# CONFIG_MCU.net
KiCad netlist of a schematic drawn in Altium Designer
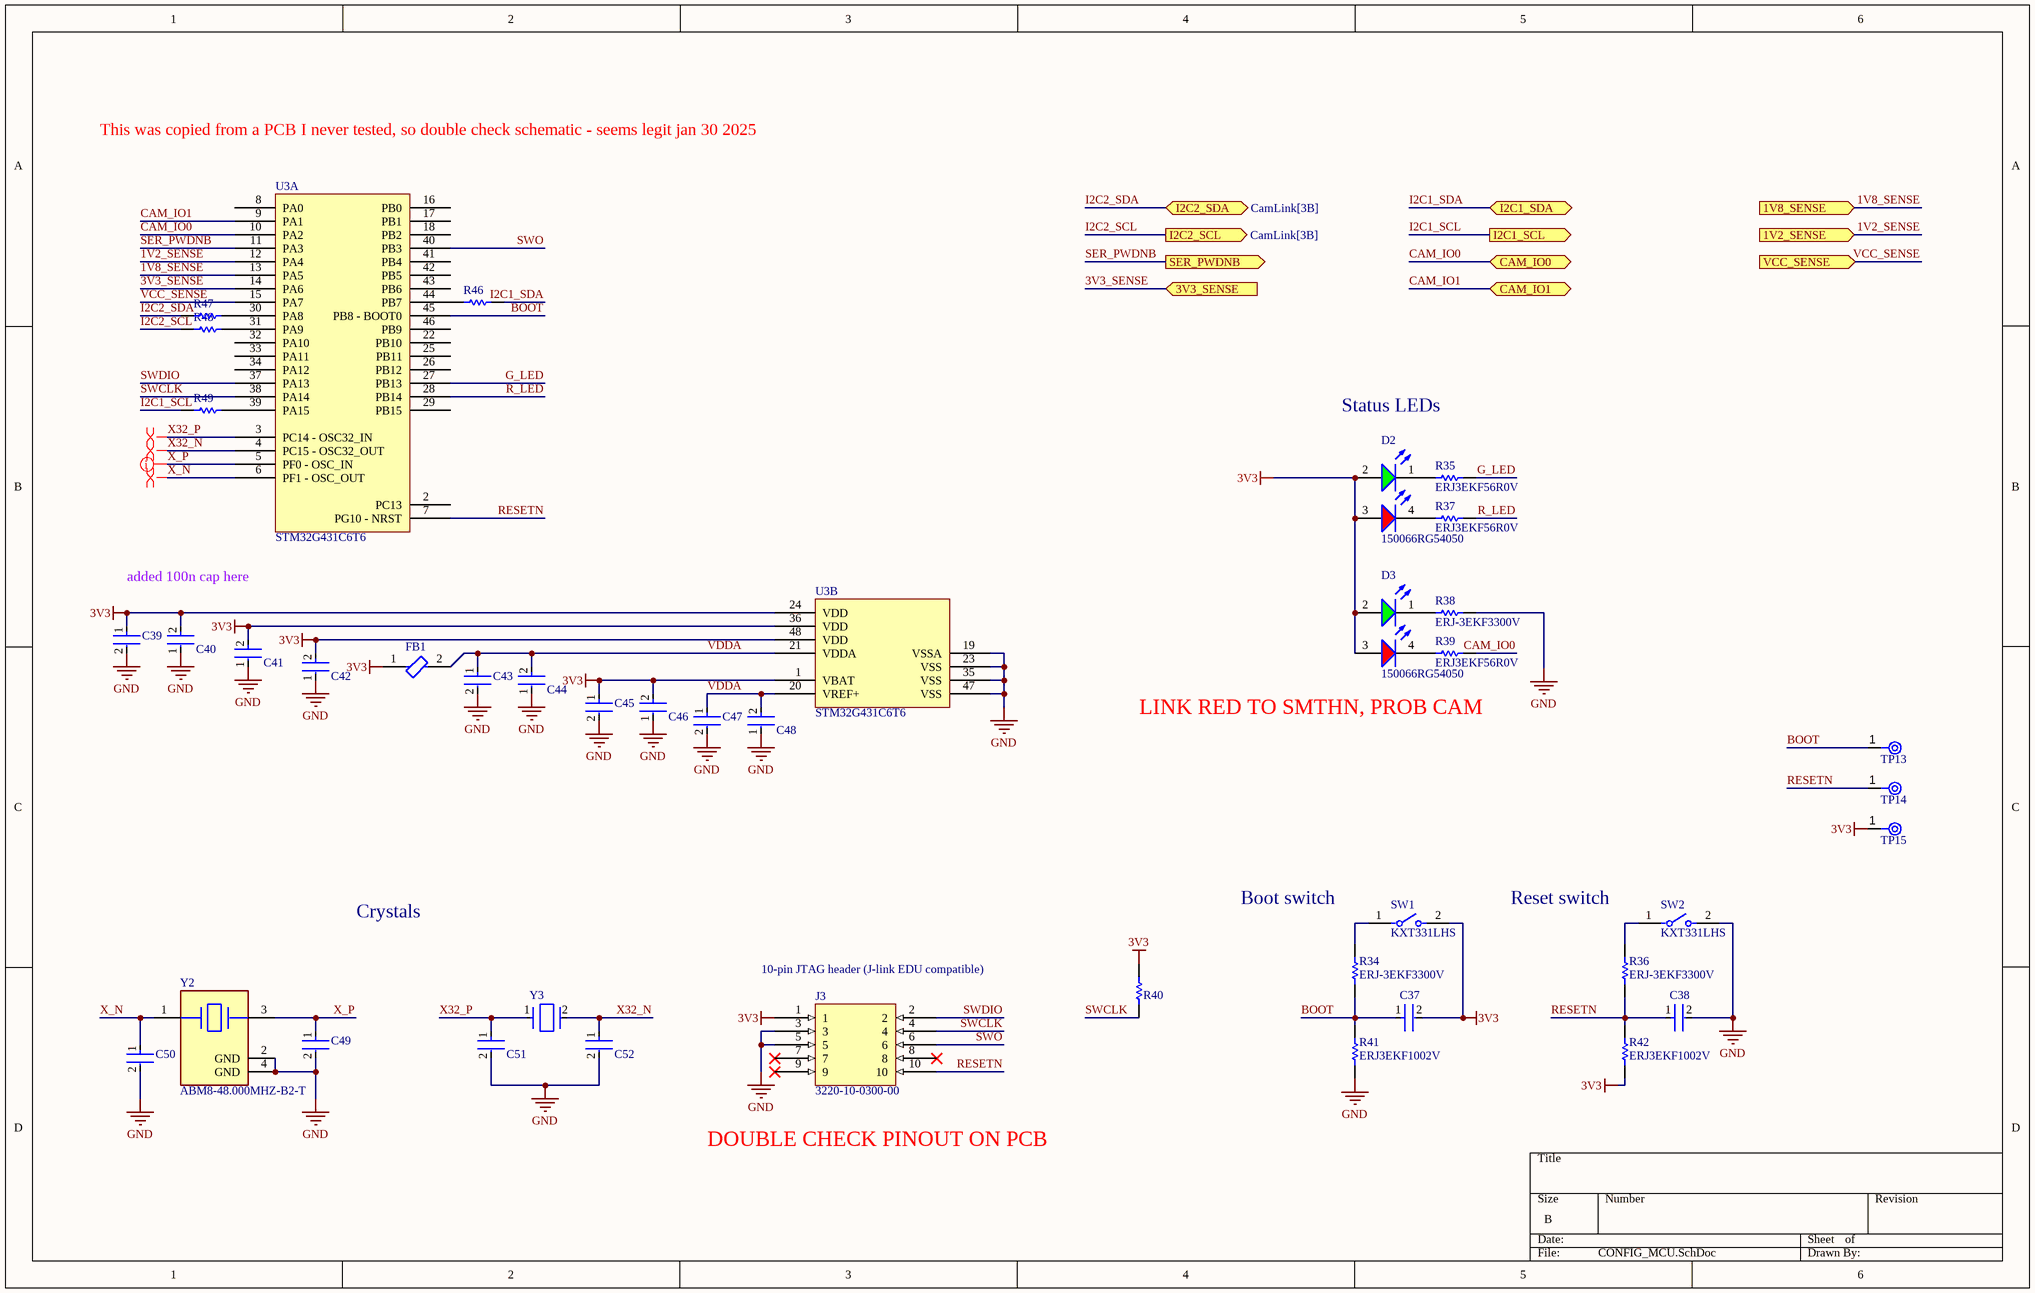
[diagram p0: CONFIG_MCU.SchDoc]

(export (version "E")
  (design (tool "Eeschema 10.0.6"))
  (components
    (comp (ref "C37")
      (value "C0402C104K8PACTU")
      (footprint "FP-C0402-BB-MFG")
      (description "CAP CER 0.1UF 10V X5R 0402")
      (fields (field (name "MANUFACTURER") "Kemet") (field (name "TOLERANCE") "0.1"))
      (libsource (lib "Altium Content Vault") (part "b4654b650e69147ec39a6b967a45e02"))
    )
    (comp (ref "C38")
      (value "C0402C104K8PACTU")
      (footprint "FP-C0402-BB-MFG")
      (description "CAP CER 0.1UF 10V X5R 0402")
      (fields (field (name "MANUFACTURER") "Kemet") (field (name "TOLERANCE") "0.1"))
      (libsource (lib "Altium Content Vault") (part "b4654b650e69147ec39a6b967a45e02"))
    )
    (comp (ref "C39")
      (value "C1005X5R1A475K050BC")
      (footprint "FP-C1005-050-0_15-MFG")
      (description "CAP CER 4.7UF 10V X5R 0402")
      (fields (field (name "TOLERANCE") "10%"))
      (libsource (lib "Altium Content Vault") (part "b4654b650e69147ec39a6b967a45e02"))
    )
    (comp (ref "C40")
      (value "GRM155R71C104KA88D")
      (footprint "FP-GRM15-MFG")
      (description "CAP CER 0.1UF 16V X7R 0402")
      (fields
        (field (name "TOLERANCE") "10%")
        (field (name "OCTOPART") "https://octopart.com/grm155r71c104ka88d-murata-196880")
      )
      (libsource (lib "Altium Content Vault") (part "236180d848d6139a670b325ea6854c9"))
    )
    (comp (ref "C41")
      (value "GRM155R71C104KA88D")
      (footprint "FP-GRM15-MFG")
      (description "CAP CER 0.1UF 16V X7R 0402")
      (fields
        (field (name "TOLERANCE") "10%")
        (field (name "OCTOPART") "https://octopart.com/grm155r71c104ka88d-murata-196880")
      )
      (libsource (lib "Altium Content Vault") (part "236180d848d6139a670b325ea6854c9"))
    )
    (comp (ref "C42")
      (value "GRM155R71C104KA88D")
      (footprint "FP-GRM15-MFG")
      (description "CAP CER 0.1UF 16V X7R 0402")
      (fields
        (field (name "TOLERANCE") "10%")
        (field (name "OCTOPART") "https://octopart.com/grm155r71c104ka88d-murata-196880")
      )
      (libsource (lib "Altium Content Vault") (part "236180d848d6139a670b325ea6854c9"))
    )
    (comp (ref "C43")
      (value "EMK105BJ105KV-F")
      (footprint "FP-0402-L_1_0_0_05-W_0_5-IPC_A")
      (description "None")
      (fields (field (name "TOLERANCE") "10%"))
      (libsource (lib "Altium Content Vault") (part "b4654b650e69147ec39a6b967a45e02"))
    )
    (comp (ref "C44")
      (value "GRM155R71C104KA88D")
      (footprint "FP-GRM15-MFG")
      (description "CAP CER 0.1UF 16V X7R 0402")
      (fields
        (field (name "TOLERANCE") "10%")
        (field (name "OCTOPART") "https://octopart.com/grm155r71c104ka88d-murata-196880")
      )
      (libsource (lib "Altium Content Vault") (part "236180d848d6139a670b325ea6854c9"))
    )
    (comp (ref "C45")
      (value "EMK105BJ105KV-F")
      (footprint "FP-0402-L_1_0_0_05-W_0_5-IPC_A")
      (description "None")
      (fields (field (name "TOLERANCE") "10%"))
      (libsource (lib "Altium Content Vault") (part "b4654b650e69147ec39a6b967a45e02"))
    )
    (comp (ref "C46")
      (value "GRM155R71C104KA88D")
      (footprint "FP-GRM15-MFG")
      (description "CAP CER 0.1UF 16V X7R 0402")
      (fields
        (field (name "TOLERANCE") "10%")
        (field (name "OCTOPART") "https://octopart.com/grm155r71c104ka88d-murata-196880")
      )
      (libsource (lib "Altium Content Vault") (part "236180d848d6139a670b325ea6854c9"))
    )
    (comp (ref "C47")
      (value "EMK105BJ105KV-F")
      (footprint "FP-0402-L_1_0_0_05-W_0_5-IPC_A")
      (description "None")
      (fields (field (name "TOLERANCE") "10%"))
      (libsource (lib "Altium Content Vault") (part "b4654b650e69147ec39a6b967a45e02"))
    )
    (comp (ref "C48")
      (value "GRM155R71C104KA88D")
      (footprint "FP-GRM15-MFG")
      (description "CAP CER 0.1UF 16V X7R 0402")
      (fields
        (field (name "TOLERANCE") "10%")
        (field (name "OCTOPART") "https://octopart.com/grm155r71c104ka88d-murata-196880")
      )
      (libsource (lib "Altium Content Vault") (part "236180d848d6139a670b325ea6854c9"))
    )
    (comp (ref "C49")
      (value "C0402C689C5GACTU")
      (footprint "FP-C0402-BB-MFG")
      (description "CAP CER 6.8PF 50V NP0 0402")
      (fields
        (field (name "OCTOPART") "https://octopart.com/c0402c689c5gactu-kemet-9143567")
        (field (name "MANUFACTURER") "Kemet")
      )
      (libsource (lib "Altium Content Vault") (part "b4654b650e69147ec39a6b967a45e02"))
    )
    (comp (ref "C50")
      (value "C0402C689C5GACTU")
      (footprint "FP-C0402-BB-MFG")
      (description "CAP CER 6.8PF 50V NP0 0402")
      (fields
        (field (name "OCTOPART") "https://octopart.com/c0402c689c5gactu-kemet-9143567")
        (field (name "MANUFACTURER") "Kemet")
      )
      (libsource (lib "Altium Content Vault") (part "b4654b650e69147ec39a6b967a45e02"))
    )
    (comp (ref "C51")
      (value "04025A180FAT2A")
      (footprint "FP-0402-L_1_0_1-W_0_5_0_1-IPC_A")
      (description "General Purpose Ceramic Capacitor, 0402, 18pF, 1%, C0G, 30ppm/°C, 50V")
      (fields (field (name "TOLERANCE") "1%"))
      (libsource (lib "Altium Content Vault") (part "b4654b650e69147ec39a6b967a45e02"))
    )
    (comp (ref "C52")
      (value "04025A180FAT2A")
      (footprint "FP-0402-L_1_0_1-W_0_5_0_1-IPC_A")
      (description "General Purpose Ceramic Capacitor, 0402, 18pF, 1%, C0G, 30ppm/°C, 50V")
      (fields (field (name "TOLERANCE") "1%"))
      (libsource (lib "Altium Content Vault") (part "b4654b650e69147ec39a6b967a45e02"))
    )
    (comp (ref "D2")
      (value "150066RG54050")
      (footprint "WL-SBCD_0606")
      (description "Led, Red/Grn, 180Mcd/230Mcd, 624Nm/525Nm Rohs Compliant: Yes")
      (fields (field (name "SOURCE") "rgled.SchLib"))
      (libsource (lib "Space Concordia") (part "CMP-004-00034-2"))
    )
    (comp (ref "D3")
      (value "150066RG54050")
      (footprint "WL-SBCD_0606")
      (description "Led, Red/Grn, 180Mcd/230Mcd, 624Nm/525Nm Rohs Compliant: Yes")
      (fields (field (name "SOURCE") "rgled.SchLib"))
      (libsource (lib "Space Concordia") (part "CMP-004-00034-2"))
    )
    (comp (ref "FB1")
      (value "BLM15PX601SN1D")
      (footprint "FP-BLM15-0_05-MFG")
      (description "Chip Ferrite Bead, 0402, 600Ω @ 100MHz, 0.23Ω, 25%, 900mA")
      (fields (field (name "TOLERANCE") "25%"))
      (libsource (lib "Altium Content Vault") (part "5f30dd21d616792df468990f7003faa"))
    )
    (comp (ref "J3")
      (value "3220-10-0300-00")
      (footprint "3220-10-0300-00-Footprint-1")
      (description "CONN HEADER SMD 10POS 1.27MM")
      (libsource (lib "Space Concordia") (part "3220-10-0300-00"))
    )
    (comp (ref "R34")
      (value "ERJ-3EKF3300V")
      (footprint "RESC1608X55X30LL15T15")
      (description "Chip Resistor, 330 Ohm, +/- 1%, 0.1 W, -55 to 155 degC, 0603 (1608 Metric), RoHS, Tape and Reel")
      (libsource (lib "Altium Content Vault") (part "RES-2"))
    )
    (comp (ref "R35")
      (value "ERJ3EKF56R0V")
      (footprint "RESC1608X55X30NL15T15")
      (fields (field (name "MANUFACTURER") "Panasonic"))
      (libsource (lib "Altium Content Vault") (part "RES"))
    )
    (comp (ref "R36")
      (value "ERJ-3EKF3300V")
      (footprint "RESC1608X55X30LL15T15")
      (description "Chip Resistor, 330 Ohm, +/- 1%, 0.1 W, -55 to 155 degC, 0603 (1608 Metric), RoHS, Tape and Reel")
      (libsource (lib "Altium Content Vault") (part "RES-2"))
    )
    (comp (ref "R37")
      (value "ERJ3EKF56R0V")
      (footprint "RESC1608X55X30NL15T15")
      (fields (field (name "MANUFACTURER") "Panasonic"))
      (libsource (lib "Altium Content Vault") (part "RES"))
    )
    (comp (ref "R38")
      (value "ERJ-3EKF3300V")
      (footprint "RESC1608X55X30LL15T15")
      (description "Chip Resistor, 330 Ohm, +/- 1%, 0.1 W, -55 to 155 degC, 0603 (1608 Metric), RoHS, Tape and Reel")
      (libsource (lib "Altium Content Vault") (part "RES-2"))
    )
    (comp (ref "R39")
      (value "ERJ3EKF56R0V")
      (footprint "RESC1608X55X30NL15T15")
      (fields (field (name "MANUFACTURER") "Panasonic"))
      (libsource (lib "Altium Content Vault") (part "RES"))
    )
    (comp (ref "R40")
      (value "ERJ3EKF1002V")
      (footprint "RESC1609X55X30LL15T15")
      (description "Chip Resistor, 10 KOhm, +/- 1%, 0.1 W, -55 to 155 degC, 0603 (1608 Metric), RoHS, Tape and Reel")
      (fields (field (name "TOLERANCE") "1%") (field (name "MANUFACTURER") "Panasonic"))
      (libsource (lib "Altium Content Vault") (part "RES-2"))
    )
    (comp (ref "R41")
      (value "ERJ3EKF1002V")
      (footprint "RESC1609X55X30LL15T15")
      (description "Chip Resistor, 10 KOhm, +/- 1%, 0.1 W, -55 to 155 degC, 0603 (1608 Metric), RoHS, Tape and Reel")
      (fields (field (name "TOLERANCE") "1%") (field (name "MANUFACTURER") "Panasonic"))
      (libsource (lib "Altium Content Vault") (part "RES-2"))
    )
    (comp (ref "R42")
      (value "ERJ3EKF1002V")
      (footprint "RESC1609X55X30LL15T15")
      (description "Chip Resistor, 10 KOhm, +/- 1%, 0.1 W, -55 to 155 degC, 0603 (1608 Metric), RoHS, Tape and Reel")
      (fields (field (name "TOLERANCE") "1%") (field (name "MANUFACTURER") "Panasonic"))
      (libsource (lib "Altium Content Vault") (part "RES-2"))
    )
    (comp (ref "R46")
      (value "RC0402JR-070RL")
      (footprint "RESC1005X40X25NL05T10")
      (fields (field (name "MANUFACTURER") "Yageo / Phycomp"))
      (libsource (lib "Altium Content Vault") (part "RES"))
    )
    (comp (ref "R47")
      (value "RC0402JR-070RL")
      (footprint "RESC1005X40X25NL05T10")
      (fields (field (name "MANUFACTURER") "Yageo / Phycomp"))
      (libsource (lib "Altium Content Vault") (part "RES"))
    )
    (comp (ref "R48")
      (value "RC0402JR-070RL")
      (footprint "RESC1005X40X25NL05T10")
      (fields (field (name "MANUFACTURER") "Yageo / Phycomp"))
      (libsource (lib "Altium Content Vault") (part "RES"))
    )
    (comp (ref "R49")
      (value "RC0402JR-070RL")
      (footprint "RESC1005X40X25NL05T10")
      (fields (field (name "MANUFACTURER") "Yageo / Phycomp"))
      (libsource (lib "Altium Content Vault") (part "RES"))
    )
    (comp (ref "SW1")
      (value "KXT331LHS")
      (footprint "FP-KXT331LHS-MFG")
      (description "SWITCH TACTILE SPST-NO 0.02A 15V")
      (libsource (lib "Altium Content Vault") (part "bb27bde45df87f1f469753f287ef5ae"))
    )
    (comp (ref "SW2")
      (value "KXT331LHS")
      (footprint "FP-KXT331LHS-MFG")
      (description "SWITCH TACTILE SPST-NO 0.02A 15V")
      (libsource (lib "Altium Content Vault") (part "bb27bde45df87f1f469753f287ef5ae"))
    )
    (comp (ref "TP13")
      (value "TPAD6R")
      (footprint "New footprint 1")
      (description "Test Point .6mm")
      (libsource (lib "Space Concordia") (part "TP"))
    )
    (comp (ref "TP14")
      (value "TPAD6R")
      (footprint "New footprint 1")
      (description "Test Point .6mm")
      (libsource (lib "Space Concordia") (part "TP"))
    )
    (comp (ref "TP15")
      (value "TPAD6R")
      (footprint "New footprint 1")
      (description "Test Point .6mm")
      (libsource (lib "Space Concordia") (part "TP"))
    )
    (comp (ref "U3")
      (value "STM32G431C6T6")
      (footprint "TSQFP50P900X900X160-48N")
      (description "IC MCU 32BIT 32KB FLASH 48LQFP")
      (libsource (lib "Space Concordia") (part "STM32G431C6T6"))
    )
    (comp (ref "Y2")
      (value "ABM8-48.000MHZ-B2-T")
      (footprint "FP-ABM8-MFG")
      (description "Crystal 48MHz ±20ppm 18pF SMD-4 3.2mm x 2.5mm")
      (fields (field (name "TOLERANCE") "20ppm"))
      (libsource (lib "Altium Content Vault") (part "dfdb7f9a12507849fb681da9a70121c"))
    )
    (comp (ref "Y3")
      (value "ECS-.327-12.5-1210-TR")
      (footprint "FP-ECX-1210-MFG")
      (description "CRYSTAL 32.7680KHZ 12.5PF SMD")
      (fields
        (field (name "OCTOPART") "https://octopart.com/ecs-.327-12.5-1210-tr-ecs+international-81221340")
        (field (name "TOLERANCE") "20ppm")
      )
      (libsource (lib "Altium Content Vault") (part "99724985039315a44fd0d1401b84e49"))
    )
  )
  (nets
    (net (code "1") (name "/1V2_SENSE") (class "Default")
      (node (ref "U3") (pin "12") (pinfunction "PA4_12") (pintype "passive"))
    )
    (net (code "2") (name "/1V8_SENSE") (class "Default")
      (node (ref "U3") (pin "13") (pinfunction "PA5_13") (pintype "passive"))
    )
    (net (code "3") (name "/3V3_SENSE") (class "Default")
      (node (ref "U3") (pin "14") (pinfunction "PA6_14") (pintype "passive"))
    )
    (net (code "4") (name "/BOOT") (class "Default")
      (node (ref "C37") (pin "1") (pinfunction "1_1") (pintype "passive"))
      (node (ref "R34") (pin "1") (pinfunction "1_1") (pintype "passive"))
      (node (ref "R41") (pin "2") (pinfunction "2_2") (pintype "passive"))
      (node (ref "TP13") (pin "1") (pinfunction "TP_1") (pintype "passive"))
      (node (ref "U3") (pin "45") (pinfunction "PB8_-_BOOT0_45") (pintype "passive"))
    )
    (net (code "5") (name "/CAM_IO0") (class "Default")
      (node (ref "R39") (pin "1") (pinfunction "1_1") (pintype "passive"))
      (node (ref "U3") (pin "10") (pinfunction "PA2_10") (pintype "passive"))
    )
    (net (code "6") (name "/CAM_IO1") (class "Default")
      (node (ref "U3") (pin "9") (pinfunction "PA1_9") (pintype "passive"))
    )
    (net (code "7") (name "/G_LED") (class "Default")
      (node (ref "R35") (pin "1") (pinfunction "1_1") (pintype "passive"))
      (node (ref "U3") (pin "27") (pinfunction "PB13_27") (pintype "passive"))
    )
    (net (code "8") (name "/I2C1_SCL") (class "Default")
      (node (ref "R49") (pin "1") (pinfunction "1_1") (pintype "passive"))
    )
    (net (code "9") (name "/I2C1_SDA") (class "Default")
      (node (ref "R46") (pin "2") (pinfunction "2_2") (pintype "passive"))
    )
    (net (code "10") (name "/I2C2_SCL") (class "Default")
      (node (ref "R48") (pin "1") (pinfunction "1_1") (pintype "passive"))
    )
    (net (code "11") (name "/I2C2_SDA") (class "Default")
      (node (ref "R47") (pin "1") (pinfunction "1_1") (pintype "passive"))
    )
    (net (code "12") (name "/RESETN") (class "Default")
      (node (ref "C38") (pin "1") (pinfunction "1_1") (pintype "passive"))
      (node (ref "J3") (pin "10") (pinfunction "10_10") (pintype "input"))
      (node (ref "R36") (pin "1") (pinfunction "1_1") (pintype "passive"))
      (node (ref "R42") (pin "2") (pinfunction "2_2") (pintype "passive"))
      (node (ref "TP14") (pin "1") (pinfunction "TP_1") (pintype "passive"))
      (node (ref "U3") (pin "7") (pinfunction "PG10_-_NRST_7") (pintype "passive"))
    )
    (net (code "13") (name "/R_LED") (class "Default")
      (node (ref "R37") (pin "1") (pinfunction "1_1") (pintype "passive"))
      (node (ref "U3") (pin "28") (pinfunction "PB14_28") (pintype "passive"))
    )
    (net (code "14") (name "/SER_PWDNB") (class "Default")
      (node (ref "U3") (pin "11") (pinfunction "PA3_11") (pintype "passive"))
    )
    (net (code "15") (name "/SWCLK") (class "Default")
      (node (ref "J3") (pin "4") (pinfunction "4_4") (pintype "input"))
      (node (ref "R40") (pin "2") (pinfunction "2_2") (pintype "passive"))
      (node (ref "U3") (pin "38") (pinfunction "PA14_38") (pintype "passive"))
    )
    (net (code "16") (name "/SWDIO") (class "Default")
      (node (ref "J3") (pin "2") (pinfunction "2_2") (pintype "input"))
      (node (ref "U3") (pin "37") (pinfunction "PA13_37") (pintype "passive"))
    )
    (net (code "17") (name "/SWO") (class "Default")
      (node (ref "J3") (pin "6") (pinfunction "6_6") (pintype "input"))
      (node (ref "U3") (pin "40") (pinfunction "PB3_40") (pintype "passive"))
    )
    (net (code "18") (name "/VCC_SENSE") (class "Default")
      (node (ref "U3") (pin "15") (pinfunction "PA7_15") (pintype "passive"))
    )
    (net (code "19") (name "/VDDA") (class "Default")
      (node (ref "C43") (pin "1") (pinfunction "1_1") (pintype "passive"))
      (node (ref "C44") (pin "2") (pinfunction "2_2") (pintype "passive"))
      (node (ref "C47") (pin "1") (pinfunction "1_1") (pintype "passive"))
      (node (ref "C48") (pin "2") (pinfunction "2_2") (pintype "passive"))
      (node (ref "FB1") (pin "2") (pinfunction "2_2") (pintype "passive"))
      (node (ref "U3") (pin "20") (pinfunction "VREF+_20") (pintype "power_in"))
      (node (ref "U3") (pin "21") (pinfunction "VDDA_21") (pintype "power_in"))
    )
    (net (code "20") (name "/X32_N") (class "Default")
      (node (ref "C52") (pin "1") (pinfunction "1_1") (pintype "passive"))
      (node (ref "U3") (pin "4") (pinfunction "PC15_-_OSC32_OUT_4") (pintype "passive"))
      (node (ref "Y3") (pin "2") (pinfunction "Out/In_2") (pintype "passive"))
    )
    (net (code "21") (name "/X32_P") (class "Default")
      (node (ref "C51") (pin "1") (pinfunction "1_1") (pintype "passive"))
      (node (ref "U3") (pin "3") (pinfunction "PC14_-_OSC32_IN_3") (pintype "passive"))
      (node (ref "Y3") (pin "1") (pinfunction "In/Out_1") (pintype "passive"))
    )
    (net (code "22") (name "/X_N") (class "Default")
      (node (ref "C50") (pin "1") (pinfunction "1_1") (pintype "passive"))
      (node (ref "U3") (pin "6") (pinfunction "PF1_-_OSC_OUT_6") (pintype "passive"))
      (node (ref "Y2") (pin "1") (pinfunction "1_1") (pintype "passive"))
    )
    (net (code "23") (name "/X_P") (class "Default")
      (node (ref "C49") (pin "1") (pinfunction "1_1") (pintype "passive"))
      (node (ref "U3") (pin "5") (pinfunction "PF0_-_OSC_IN_5") (pintype "passive"))
      (node (ref "Y2") (pin "3") (pinfunction "3_3") (pintype "passive"))
    )
    (net (code "24") (name "3V3") (class "Default")
      (node (ref "C37") (pin "2") (pinfunction "2_2") (pintype "passive"))
      (node (ref "C39") (pin "1") (pinfunction "1_1") (pintype "passive"))
      (node (ref "C40") (pin "2") (pinfunction "2_2") (pintype "passive"))
      (node (ref "C41") (pin "2") (pinfunction "2_2") (pintype "passive"))
      (node (ref "C42") (pin "2") (pinfunction "2_2") (pintype "passive"))
      (node (ref "C45") (pin "1") (pinfunction "1_1") (pintype "passive"))
      (node (ref "C46") (pin "2") (pinfunction "2_2") (pintype "passive"))
      (node (ref "D2") (pin "2") (pinfunction "A_2") (pintype "passive"))
      (node (ref "D2") (pin "3") (pinfunction "A_3") (pintype "passive"))
      (node (ref "D3") (pin "2") (pinfunction "A_2") (pintype "passive"))
      (node (ref "D3") (pin "3") (pinfunction "A_3") (pintype "passive"))
      (node (ref "FB1") (pin "1") (pinfunction "1_1") (pintype "passive"))
      (node (ref "J3") (pin "1") (pinfunction "1_1") (pintype "input"))
      (node (ref "R40") (pin "1") (pinfunction "1_1") (pintype "passive"))
      (node (ref "R42") (pin "1") (pinfunction "1_1") (pintype "passive"))
      (node (ref "SW1") (pin "2") (pinfunction "2_2") (pintype "passive"))
      (node (ref "TP15") (pin "1") (pinfunction "TP_1") (pintype "passive"))
      (node (ref "U3") (pin "1") (pinfunction "VBAT_1") (pintype "power_in"))
      (node (ref "U3") (pin "24") (pinfunction "VDD_24") (pintype "power_in"))
      (node (ref "U3") (pin "36") (pinfunction "VDD_36") (pintype "power_in"))
      (node (ref "U3") (pin "48") (pinfunction "VDD_48") (pintype "power_in"))
    )
    (net (code "25") (name "GND") (class "Default")
      (node (ref "C38") (pin "2") (pinfunction "2_2") (pintype "passive"))
      (node (ref "C39") (pin "2") (pinfunction "2_2") (pintype "passive"))
      (node (ref "C40") (pin "1") (pinfunction "1_1") (pintype "passive"))
      (node (ref "C41") (pin "1") (pinfunction "1_1") (pintype "passive"))
      (node (ref "C42") (pin "1") (pinfunction "1_1") (pintype "passive"))
      (node (ref "C43") (pin "2") (pinfunction "2_2") (pintype "passive"))
      (node (ref "C44") (pin "1") (pinfunction "1_1") (pintype "passive"))
      (node (ref "C45") (pin "2") (pinfunction "2_2") (pintype "passive"))
      (node (ref "C46") (pin "1") (pinfunction "1_1") (pintype "passive"))
      (node (ref "C47") (pin "2") (pinfunction "2_2") (pintype "passive"))
      (node (ref "C48") (pin "1") (pinfunction "1_1") (pintype "passive"))
      (node (ref "C49") (pin "2") (pinfunction "2_2") (pintype "passive"))
      (node (ref "C50") (pin "2") (pinfunction "2_2") (pintype "passive"))
      (node (ref "C51") (pin "2") (pinfunction "2_2") (pintype "passive"))
      (node (ref "C52") (pin "2") (pinfunction "2_2") (pintype "passive"))
      (node (ref "J3") (pin "3") (pinfunction "3_3") (pintype "input"))
      (node (ref "J3") (pin "5") (pinfunction "5_5") (pintype "input"))
      (node (ref "R38") (pin "2") (pinfunction "2_2") (pintype "passive"))
      (node (ref "R41") (pin "1") (pinfunction "1_1") (pintype "passive"))
      (node (ref "SW2") (pin "2") (pinfunction "2_2") (pintype "passive"))
      (node (ref "U3") (pin "19") (pinfunction "VSSA_19") (pintype "power_in"))
      (node (ref "U3") (pin "23") (pinfunction "VSS_23") (pintype "power_in"))
      (node (ref "U3") (pin "35") (pinfunction "VSS_35") (pintype "power_in"))
      (node (ref "U3") (pin "47") (pinfunction "VSS_47") (pintype "power_in"))
      (node (ref "Y2") (pin "2") (pinfunction "GND_2") (pintype "power_in"))
      (node (ref "Y2") (pin "4") (pinfunction "GND_4") (pintype "power_in"))
    )
    (net (code "26") (name "Net-(D2-K-Pad1)") (class "Default")
      (node (ref "D2") (pin "1") (pinfunction "K_1") (pintype "passive"))
      (node (ref "R35") (pin "2") (pinfunction "2_2") (pintype "passive"))
    )
    (net (code "27") (name "Net-(D2-K-Pad4)") (class "Default")
      (node (ref "D2") (pin "4") (pinfunction "K_4") (pintype "passive"))
      (node (ref "R37") (pin "2") (pinfunction "2_2") (pintype "passive"))
    )
    (net (code "28") (name "Net-(D3-K-Pad1)") (class "Default")
      (node (ref "D3") (pin "1") (pinfunction "K_1") (pintype "passive"))
      (node (ref "R38") (pin "1") (pinfunction "1_1") (pintype "passive"))
    )
    (net (code "29") (name "Net-(D3-K-Pad4)") (class "Default")
      (node (ref "D3") (pin "4") (pinfunction "K_4") (pintype "passive"))
      (node (ref "R39") (pin "2") (pinfunction "2_2") (pintype "passive"))
    )
    (net (code "30") (name "Net-(R34-Pad2)") (class "Default")
      (node (ref "R34") (pin "2") (pinfunction "2_2") (pintype "passive"))
      (node (ref "SW1") (pin "1") (pinfunction "1_1") (pintype "passive"))
    )
    (net (code "31") (name "Net-(R36-Pad2)") (class "Default")
      (node (ref "R36") (pin "2") (pinfunction "2_2") (pintype "passive"))
      (node (ref "SW2") (pin "1") (pinfunction "1_1") (pintype "passive"))
    )
    (net (code "32") (name "Net-(U3A-PA8)") (class "Default")
      (node (ref "R47") (pin "2") (pinfunction "2_2") (pintype "passive"))
      (node (ref "U3") (pin "30") (pinfunction "PA8_30") (pintype "passive"))
    )
    (net (code "33") (name "Net-(U3A-PA9)") (class "Default")
      (node (ref "R48") (pin "2") (pinfunction "2_2") (pintype "passive"))
      (node (ref "U3") (pin "31") (pinfunction "PA9_31") (pintype "passive"))
    )
    (net (code "34") (name "Net-(U3A-PA15)") (class "Default")
      (node (ref "R49") (pin "2") (pinfunction "2_2") (pintype "passive"))
      (node (ref "U3") (pin "39") (pinfunction "PA15_39") (pintype "passive"))
    )
    (net (code "35") (name "Net-(U3A-PB7)") (class "Default")
      (node (ref "R46") (pin "1") (pinfunction "1_1") (pintype "passive"))
      (node (ref "U3") (pin "44") (pinfunction "PB7_44") (pintype "passive"))
    )
    (net (code "36") (name "unconnected-(J3-Pad7)") (class "Default")
      (node (ref "J3") (pin "7") (pinfunction "7_7") (pintype "input+no_connect"))
    )
    (net (code "37") (name "unconnected-(J3-Pad8)") (class "Default")
      (node (ref "J3") (pin "8") (pinfunction "8_8") (pintype "input+no_connect"))
    )
    (net (code "38") (name "unconnected-(J3-Pad9)") (class "Default")
      (node (ref "J3") (pin "9") (pinfunction "9_9") (pintype "input+no_connect"))
    )
    (net (code "39") (name "unconnected-(U3A-PA0-Pad8)") (class "Default")
      (node (ref "U3") (pin "8") (pinfunction "PA0_8") (pintype "passive"))
    )
    (net (code "40") (name "unconnected-(U3A-PA10-Pad32)") (class "Default")
      (node (ref "U3") (pin "32") (pinfunction "PA10_32") (pintype "passive"))
    )
    (net (code "41") (name "unconnected-(U3A-PA11-Pad33)") (class "Default")
      (node (ref "U3") (pin "33") (pinfunction "PA11_33") (pintype "passive"))
    )
    (net (code "42") (name "unconnected-(U3A-PA12-Pad34)") (class "Default")
      (node (ref "U3") (pin "34") (pinfunction "PA12_34") (pintype "passive"))
    )
    (net (code "43") (name "unconnected-(U3A-PB0-Pad16)") (class "Default")
      (node (ref "U3") (pin "16") (pinfunction "PB0_16") (pintype "passive"))
    )
    (net (code "44") (name "unconnected-(U3A-PB1-Pad17)") (class "Default")
      (node (ref "U3") (pin "17") (pinfunction "PB1_17") (pintype "passive"))
    )
    (net (code "45") (name "unconnected-(U3A-PB2-Pad18)") (class "Default")
      (node (ref "U3") (pin "18") (pinfunction "PB2_18") (pintype "passive"))
    )
    (net (code "46") (name "unconnected-(U3A-PB4-Pad41)") (class "Default")
      (node (ref "U3") (pin "41") (pinfunction "PB4_41") (pintype "passive"))
    )
    (net (code "47") (name "unconnected-(U3A-PB5-Pad42)") (class "Default")
      (node (ref "U3") (pin "42") (pinfunction "PB5_42") (pintype "passive"))
    )
    (net (code "48") (name "unconnected-(U3A-PB6-Pad43)") (class "Default")
      (node (ref "U3") (pin "43") (pinfunction "PB6_43") (pintype "passive"))
    )
    (net (code "49") (name "unconnected-(U3A-PB9-Pad46)") (class "Default")
      (node (ref "U3") (pin "46") (pinfunction "PB9_46") (pintype "passive"))
    )
    (net (code "50") (name "unconnected-(U3A-PB10-Pad22)") (class "Default")
      (node (ref "U3") (pin "22") (pinfunction "PB10_22") (pintype "passive"))
    )
    (net (code "51") (name "unconnected-(U3A-PB11-Pad25)") (class "Default")
      (node (ref "U3") (pin "25") (pinfunction "PB11_25") (pintype "passive"))
    )
    (net (code "52") (name "unconnected-(U3A-PB12-Pad26)") (class "Default")
      (node (ref "U3") (pin "26") (pinfunction "PB12_26") (pintype "passive"))
    )
    (net (code "53") (name "unconnected-(U3A-PB15-Pad29)") (class "Default")
      (node (ref "U3") (pin "29") (pinfunction "PB15_29") (pintype "passive"))
    )
    (net (code "54") (name "unconnected-(U3A-PC13-Pad2)") (class "Default")
      (node (ref "U3") (pin "2") (pinfunction "PC13_2") (pintype "passive"))
    )
  )
)
